# Power.net
KiCad netlist of a schematic drawn in Altium Designer
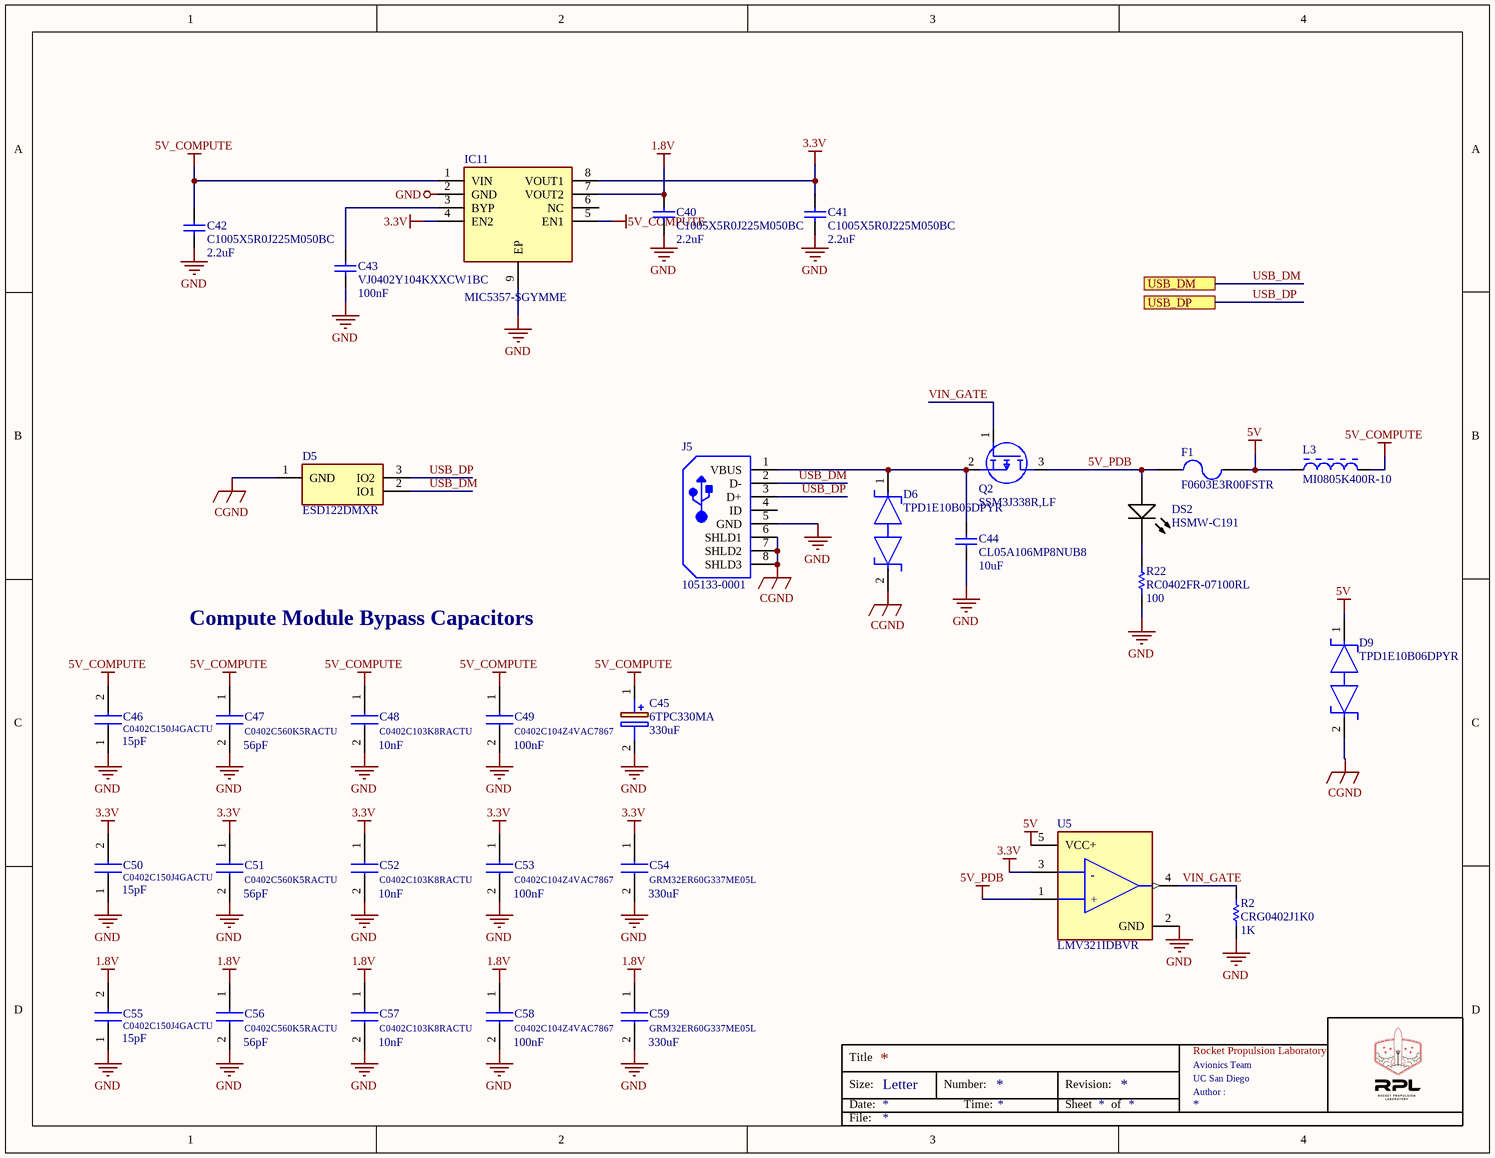
[diagram p0: Power.SchDoc]

(export (version "E")
  (design (tool "Eeschema 10.0.6"))
  (components
    (comp (ref "C40")
      (value "C1005X5R0J225M050BC")
      (footprint "0402")
      (description "Capacitor")
      (fields (field (name "ALTIUM_VALUE") "2.2uF") (field (name "PUBLISHER") "Altium Limited"))
      (libsource (lib "Miscellaneous Devices") (part "Cap"))
    )
    (comp (ref "C41")
      (value "C1005X5R0J225M050BC")
      (footprint "0402")
      (description "Capacitor")
      (fields (field (name "ALTIUM_VALUE") "2.2uF") (field (name "PUBLISHER") "Altium Limited"))
      (libsource (lib "Miscellaneous Devices") (part "Cap"))
    )
    (comp (ref "C42")
      (value "C1005X5R0J225M050BC")
      (footprint "0402")
      (description "Capacitor")
      (fields (field (name "ALTIUM_VALUE") "2.2uF") (field (name "PUBLISHER") "Altium Limited"))
      (libsource (lib "Miscellaneous Devices") (part "Cap"))
    )
    (comp (ref "C43")
      (value "VJ0402Y104KXXCW1BC")
      (footprint "0402")
      (description "Capacitor")
      (fields (field (name "ALTIUM_VALUE") "100nF") (field (name "PUBLISHER") "Altium Limited"))
      (libsource (lib "Miscellaneous Devices") (part "Cap"))
    )
    (comp (ref "C44")
      (value "CL05A106MP8NUB8")
      (footprint "0402")
      (description "Capacitor")
      (fields (field (name "ALTIUM_VALUE") "10uF") (field (name "PUBLISHER") "Altium Limited"))
      (libsource (lib "Miscellaneous Devices") (part "Cap"))
    )
    (comp (ref "C45")
      (value "6TPC330MA")
      (footprint "PcbLib1:CAPPM7343X200N")
      (description "Capacitor Polarised")
      (fields (field (name "MOUSER PART NUMBER") "667-6TPC330MA") (field (name "ALTIUM_VALUE") "330uF"))
      (libsource (lib "*") (part "6TPC330MA"))
    )
    (comp (ref "C46")
      (value "C0402C150J4GACTU")
      (footprint "PcbLib1:CAPC1005X90N")
      (description "Capacitor")
      (fields (field (name "MOUSER PART NUMBER") "80-C0402C150J4G") (field (name "ALTIUM_VALUE") "15pF"))
      (libsource (lib "*") (part "C0402C150J4GACTU"))
    )
    (comp (ref "C47")
      (value "C0402C560K5RACTU")
      (footprint "PcbLib1:CAPC1005X55N")
      (description "Capacitor")
      (fields (field (name "MOUSER PART NUMBER") "80-C0402C560K5RACTU") (field (name "ALTIUM_VALUE") "56pF"))
      (libsource (lib "*") (part "C0402C560K5RACTU"))
    )
    (comp (ref "C48")
      (value "C0402C103K8RACTU")
      (footprint "PcbLib1:CAPC1005X55N")
      (description "Capacitor")
      (fields (field (name "MOUSER PART NUMBER") "80-C0402C103K8R") (field (name "ALTIUM_VALUE") "10nF"))
      (libsource (lib "*") (part "C0402C103K8RACTU"))
    )
    (comp (ref "C49")
      (value "C0402C104Z4VAC7867")
      (footprint "PcbLib1:CAPC1005X55N")
      (description "Capacitor")
      (fields
        (field (name "MANUFACTURER_PART_NUMBER") "C0402C560K5RACTU")
        (field (name "MOUSER PART NUMBER") "80-C0402C560K5RACTU")
        (field (name "ALTIUM_VALUE") "100nF")
      )
      (libsource (lib "*") (part "C0402C560K5RACTU"))
    )
    (comp (ref "C50")
      (value "C0402C150J4GACTU")
      (footprint "PcbLib1:CAPC1005X90N")
      (description "Capacitor")
      (fields (field (name "MOUSER PART NUMBER") "80-C0402C150J4G") (field (name "ALTIUM_VALUE") "15pF"))
      (libsource (lib "*") (part "C0402C150J4GACTU"))
    )
    (comp (ref "C51")
      (value "C0402C560K5RACTU")
      (footprint "PcbLib1:CAPC1005X55N")
      (description "Capacitor")
      (fields (field (name "MOUSER PART NUMBER") "80-C0402C560K5RACTU") (field (name "ALTIUM_VALUE") "56pF"))
      (libsource (lib "*") (part "C0402C560K5RACTU"))
    )
    (comp (ref "C52")
      (value "C0402C103K8RACTU")
      (footprint "PcbLib1:CAPC1005X55N")
      (description "Capacitor")
      (fields (field (name "MOUSER PART NUMBER") "80-C0402C103K8R") (field (name "ALTIUM_VALUE") "10nF"))
      (libsource (lib "*") (part "C0402C103K8RACTU"))
    )
    (comp (ref "C53")
      (value "C0402C104Z4VAC7867")
      (footprint "PcbLib1:CAPC1005X55N")
      (description "Capacitor")
      (fields
        (field (name "MANUFACTURER_PART_NUMBER") "C0402C560K5RACTU")
        (field (name "MOUSER PART NUMBER") "80-C0402C560K5RACTU")
        (field (name "ALTIUM_VALUE") "100nF")
      )
      (libsource (lib "*") (part "C0402C560K5RACTU"))
    )
    (comp (ref "C54")
      (value "GRM32ER60G337ME05L")
      (footprint "PcbLib1:CAPC3225X280N")
      (description "Capacitor")
      (fields
        (field (name "MOUSER PART NUMBER") "81-GRM32ER60G337ME5L")
        (field (name "ALTIUM_VALUE") "330uF")
      )
      (libsource (lib "*") (part "GRM32ER60G337ME05L"))
    )
    (comp (ref "C55")
      (value "C0402C150J4GACTU")
      (footprint "PcbLib1:CAPC1005X90N")
      (description "Capacitor")
      (fields (field (name "MOUSER PART NUMBER") "80-C0402C150J4G") (field (name "ALTIUM_VALUE") "15pF"))
      (libsource (lib "*") (part "C0402C150J4GACTU"))
    )
    (comp (ref "C56")
      (value "C0402C560K5RACTU")
      (footprint "PcbLib1:CAPC1005X55N")
      (description "Capacitor")
      (fields (field (name "MOUSER PART NUMBER") "80-C0402C560K5RACTU") (field (name "ALTIUM_VALUE") "56pF"))
      (libsource (lib "*") (part "C0402C560K5RACTU"))
    )
    (comp (ref "C57")
      (value "C0402C103K8RACTU")
      (footprint "PcbLib1:CAPC1005X55N")
      (description "Capacitor")
      (fields (field (name "MOUSER PART NUMBER") "80-C0402C103K8R") (field (name "ALTIUM_VALUE") "10nF"))
      (libsource (lib "*") (part "C0402C103K8RACTU"))
    )
    (comp (ref "C58")
      (value "C0402C104Z4VAC7867")
      (footprint "PcbLib1:CAPC1005X55N")
      (description "Capacitor")
      (fields
        (field (name "MANUFACTURER_PART_NUMBER") "C0402C560K5RACTU")
        (field (name "MOUSER PART NUMBER") "80-C0402C560K5RACTU")
        (field (name "ALTIUM_VALUE") "100nF")
      )
      (libsource (lib "*") (part "C0402C560K5RACTU"))
    )
    (comp (ref "C59")
      (value "GRM32ER60G337ME05L")
      (footprint "PcbLib1:CAPC3225X280N")
      (description "Capacitor")
      (fields
        (field (name "MOUSER PART NUMBER") "81-GRM32ER60G337ME5L")
        (field (name "ALTIUM_VALUE") "330uF")
      )
      (libsource (lib "*") (part "GRM32ER60G337ME05L"))
    )
    (comp (ref "D5")
      (value "ESD122DMXR")
      (footprint "PcbLib1:DMX0003A")
      (description "TVS Diode (Bi-directional)")
      (fields (field (name "MOUSER PART NUMBER") "595-ESD122DMXR"))
      (libsource (lib "*") (part "ESD122DMXR"))
    )
    (comp (ref "D6")
      (value "TPD1E10B06DPYR")
      (footprint "FP-DPY0002A-MFG")
      (description "TVS DIODE 5.5V 14V 2X1SON")
      (libsource (lib "Altium Content Vault") (part "208e19b57522434895fa003e5d5b197"))
    )
    (comp (ref "D9")
      (value "TPD1E10B06DPYR")
      (footprint "FP-DPY0002A-MFG")
      (description "TVS DIODE 5.5V 14V 2X1SON")
      (libsource (lib "Altium Content Vault") (part "208e19b57522434895fa003e5d5b197"))
    )
    (comp (ref "DS2")
      (value "HSMW-C191")
      (footprint "AVAG-HSMW-C191_V")
      (description "LED Uni-Color White, 78 mW, 20 mA, -40 to 85 degC, 2-Pin SMD, RoHS, Tape and Reel")
      (libsource (lib "Altium Content Vault") (part "LED-WHITE-AK-2"))
    )
    (comp (ref "F1")
      (value "F0603E3R00FSTR")
      (footprint "1608[0603]")
      (description "Fuse")
      (fields (field (name "PUBLISHER") "Altium Limited"))
      (libsource (lib "Miscellaneous Devices") (part "Fuse 2"))
    )
    (comp (ref "IC11")
      (value "MIC5357-SGYMME")
      (footprint "PcbLib1:SOP65P490X104-9N")
      (description "Integrated Circuit")
      (fields (field (name "MOUSER PART NUMBER") "998-MIC5357-SGYMME"))
      (libsource (lib "*") (part "MIC5357-SGYMME"))
    )
    (comp (ref "J5")
      (value "105133-0001")
      (footprint "MOLX-105133-0001_V")
      (description "Micro-USB B Receptacle, Vertical, -30 to 85 degC, 5-Pin SMD, RoHS, Tape and Reel")
      (fields (field (name "MANUFACTURER") "Molex"))
      (libsource (lib "Altium Content Vault") (part "USB-5-3SHLD"))
    )
    (comp (ref "L3")
      (value "MI0805K400R-10")
      (footprint "LIRD-MI0805K400R-10_V")
      (description "Chip Ferrite Bead, 1.5 A, -40 to 125 degC, 2-Pin SMD (0805), RoHS, Tape and Reel")
      (fields (field (name "MANUFACTURER") "Laird"))
      (libsource (lib "Altium Content Vault") (part "IND-FB-2"))
    )
    (comp (ref "Q2")
      (value "SSM3J338R,LF")
      (footprint "PcbLib1:SSM3J332RLFT")
      (description "MOSFET (P-Channel)")
      (fields (field (name "MOUSER PART NUMBER") "757-SSM3J338RLF"))
      (libsource (lib "*") (part "SSM3J338R,LF"))
    )
    (comp (ref "R2")
      (value "CRG0402J1K0")
      (footprint "0402")
      (description "Resistor")
      (fields (field (name "ALTIUM_VALUE") "1K") (field (name "PUBLISHER") "Altium Limited"))
      (libsource (lib "Miscellaneous Devices") (part "Res1"))
    )
    (comp (ref "R22")
      (value "RC0402FR-07100RL")
      (footprint "RESC1005X40X25ML05T10")
      (fields (field (name "MANUFACTURER") "Yageo / Phycomp") (field (name "SPEC") "100"))
      (libsource (lib "Altium Content Vault") (part "RES"))
    )
    (comp (ref "U5")
      (value "LMV321IDBVR")
      (footprint "FP-DBV0005A-MFG")
      (description "IC OPAMP GP 1 CIRCUIT SOT23-5")
      (fields
        (field (name "MANUFACTURER") "Texas Instruments")
        (field (name "OCTOPART") "https://octopart.com/lmv321idbvr-texas+instruments-410381")
      )
      (libsource (lib "Altium Content Vault") (part "ec165d7f6fd2c1e6935a66fb0025aed"))
    )
  )
  (nets
    (net (code "1") (name "/USB_DM") (class "Default")
      (node (ref "D5") (pin "2") (pinfunction "IO1_2") (pintype "passive"))
      (node (ref "J5") (pin "2") (pinfunction "D-_2") (pintype "passive"))
    )
    (net (code "2") (name "/USB_DP") (class "Default")
      (node (ref "D5") (pin "3") (pinfunction "IO2_3") (pintype "passive"))
      (node (ref "J5") (pin "3") (pinfunction "D+_3") (pintype "passive"))
    )
    (net (code "3") (name "/VIN_GATE") (class "Default")
      (node (ref "Q2") (pin "1") (pinfunction "G_1") (pintype "passive"))
      (node (ref "R2") (pin "1") (pinfunction "1_1") (pintype "passive"))
      (node (ref "U5") (pin "4") (pinfunction "OUT_4") (pintype "output"))
    )
    (net (code "4") (name "1.8V") (class "Default")
      (node (ref "C40") (pin "2") (pinfunction "2_2") (pintype "passive"))
      (node (ref "C55") (pin "2") (pinfunction "2_2") (pintype "passive"))
      (node (ref "C56") (pin "1") (pinfunction "1_1") (pintype "passive"))
      (node (ref "C57") (pin "1") (pinfunction "1_1") (pintype "passive"))
      (node (ref "C58") (pin "1") (pinfunction "1_1") (pintype "passive"))
      (node (ref "C59") (pin "1") (pinfunction "1_1") (pintype "passive"))
      (node (ref "IC11") (pin "7") (pinfunction "VOUT2_7") (pintype "passive"))
    )
    (net (code "5") (name "3.3V") (class "Default")
      (node (ref "C41") (pin "2") (pinfunction "2_2") (pintype "passive"))
      (node (ref "C50") (pin "2") (pinfunction "2_2") (pintype "passive"))
      (node (ref "C51") (pin "1") (pinfunction "1_1") (pintype "passive"))
      (node (ref "C52") (pin "1") (pinfunction "1_1") (pintype "passive"))
      (node (ref "C53") (pin "1") (pinfunction "1_1") (pintype "passive"))
      (node (ref "C54") (pin "1") (pinfunction "1_1") (pintype "passive"))
      (node (ref "IC11") (pin "4") (pinfunction "EN2_4") (pintype "passive"))
      (node (ref "IC11") (pin "8") (pinfunction "VOUT1_8") (pintype "passive"))
      (node (ref "U5") (pin "3") (pinfunction "1IN-_3") (pintype "tri_state"))
    )
    (net (code "6") (name "5V") (class "Default")
      (node (ref "D9") (pin "1") (pinfunction "1_1") (pintype "passive"))
      (node (ref "F1") (pin "2") (pinfunction "2_2") (pintype "passive"))
      (node (ref "L3") (pin "1") (pinfunction "1_1") (pintype "passive"))
      (node (ref "U5") (pin "5") (pinfunction "VCC+_5") (pintype "power_in"))
    )
    (net (code "7") (name "5V_COMPUTE") (class "Default")
      (node (ref "C42") (pin "2") (pinfunction "2_2") (pintype "passive"))
      (node (ref "C45") (pin "1") (pinfunction "+_1") (pintype "passive"))
      (node (ref "C46") (pin "2") (pinfunction "2_2") (pintype "passive"))
      (node (ref "C47") (pin "1") (pinfunction "1_1") (pintype "passive"))
      (node (ref "C48") (pin "1") (pinfunction "1_1") (pintype "passive"))
      (node (ref "C49") (pin "1") (pinfunction "1_1") (pintype "passive"))
      (node (ref "IC11") (pin "1") (pinfunction "VIN_1") (pintype "passive"))
      (node (ref "IC11") (pin "5") (pinfunction "EN1_5") (pintype "passive"))
      (node (ref "L3") (pin "2") (pinfunction "2_2") (pintype "passive"))
    )
    (net (code "8") (name "5V_PDB") (class "Default")
      (node (ref "DS2") (pin "1") (pinfunction "A_1") (pintype "passive"))
      (node (ref "F1") (pin "1") (pinfunction "1_1") (pintype "passive"))
      (node (ref "Q2") (pin "3") (pinfunction "D_3") (pintype "passive"))
      (node (ref "U5") (pin "1") (pinfunction "1IN+_1") (pintype "tri_state"))
    )
    (net (code "9") (name "CGND") (class "Default")
      (node (ref "D5") (pin "1") (pinfunction "GND_1") (pintype "passive"))
      (node (ref "D6") (pin "2") (pinfunction "2_2") (pintype "passive"))
      (node (ref "D9") (pin "2") (pinfunction "2_2") (pintype "passive"))
      (node (ref "J5") (pin "6") (pinfunction "SHLD1_6") (pintype "passive"))
      (node (ref "J5") (pin "7") (pinfunction "SHLD2_7") (pintype "passive"))
      (node (ref "J5") (pin "8") (pinfunction "SHLD3_8") (pintype "passive"))
    )
    (net (code "10") (name "GND") (class "Default")
      (node (ref "C40") (pin "1") (pinfunction "1_1") (pintype "passive"))
      (node (ref "C41") (pin "1") (pinfunction "1_1") (pintype "passive"))
      (node (ref "C42") (pin "1") (pinfunction "1_1") (pintype "passive"))
      (node (ref "C43") (pin "1") (pinfunction "1_1") (pintype "passive"))
      (node (ref "C44") (pin "1") (pinfunction "1_1") (pintype "passive"))
      (node (ref "C45") (pin "2") (pinfunction "-_2") (pintype "passive"))
      (node (ref "C46") (pin "1") (pinfunction "1_1") (pintype "passive"))
      (node (ref "C47") (pin "2") (pinfunction "2_2") (pintype "passive"))
      (node (ref "C48") (pin "2") (pinfunction "2_2") (pintype "passive"))
      (node (ref "C49") (pin "2") (pinfunction "2_2") (pintype "passive"))
      (node (ref "C50") (pin "1") (pinfunction "1_1") (pintype "passive"))
      (node (ref "C51") (pin "2") (pinfunction "2_2") (pintype "passive"))
      (node (ref "C52") (pin "2") (pinfunction "2_2") (pintype "passive"))
      (node (ref "C53") (pin "2") (pinfunction "2_2") (pintype "passive"))
      (node (ref "C54") (pin "2") (pinfunction "2_2") (pintype "passive"))
      (node (ref "C55") (pin "1") (pinfunction "1_1") (pintype "passive"))
      (node (ref "C56") (pin "2") (pinfunction "2_2") (pintype "passive"))
      (node (ref "C57") (pin "2") (pinfunction "2_2") (pintype "passive"))
      (node (ref "C58") (pin "2") (pinfunction "2_2") (pintype "passive"))
      (node (ref "C59") (pin "2") (pinfunction "2_2") (pintype "passive"))
      (node (ref "IC11") (pin "2") (pinfunction "GND_2") (pintype "passive"))
      (node (ref "IC11") (pin "9") (pinfunction "EP_9") (pintype "passive"))
      (node (ref "J5") (pin "5") (pinfunction "GND_5") (pintype "passive"))
      (node (ref "R2") (pin "2") (pinfunction "2_2") (pintype "passive"))
      (node (ref "R22") (pin "1") (pinfunction "1_1") (pintype "passive"))
      (node (ref "U5") (pin "2") (pinfunction "GND_2") (pintype "power_in"))
    )
    (net (code "11") (name "Net-(DS2-K)") (class "Default")
      (node (ref "DS2") (pin "2") (pinfunction "K_2") (pintype "passive"))
      (node (ref "R22") (pin "2") (pinfunction "2_2") (pintype "passive"))
    )
    (net (code "12") (name "Net-(IC11-BYP)") (class "Default")
      (node (ref "C43") (pin "2") (pinfunction "2_2") (pintype "passive"))
      (node (ref "IC11") (pin "3") (pinfunction "BYP_3") (pintype "passive"))
    )
    (net (code "13") (name "Net-(J5-VBUS)") (class "Default")
      (node (ref "C44") (pin "2") (pinfunction "2_2") (pintype "passive"))
      (node (ref "D6") (pin "1") (pinfunction "1_1") (pintype "passive"))
      (node (ref "J5") (pin "1") (pinfunction "VBUS_1") (pintype "passive"))
      (node (ref "Q2") (pin "2") (pinfunction "S_2") (pintype "passive"))
    )
    (net (code "14") (name "unconnected-(IC11-NC-Pad6)") (class "Default")
      (node (ref "IC11") (pin "6") (pinfunction "NC_6") (pintype "passive"))
    )
    (net (code "15") (name "unconnected-(J5-ID-Pad4)") (class "Default")
      (node (ref "J5") (pin "4") (pinfunction "ID_4") (pintype "passive"))
    )
  )
)
